# uv-light-sensor.net
KiCad netlist of a schematic drawn in EAGLE
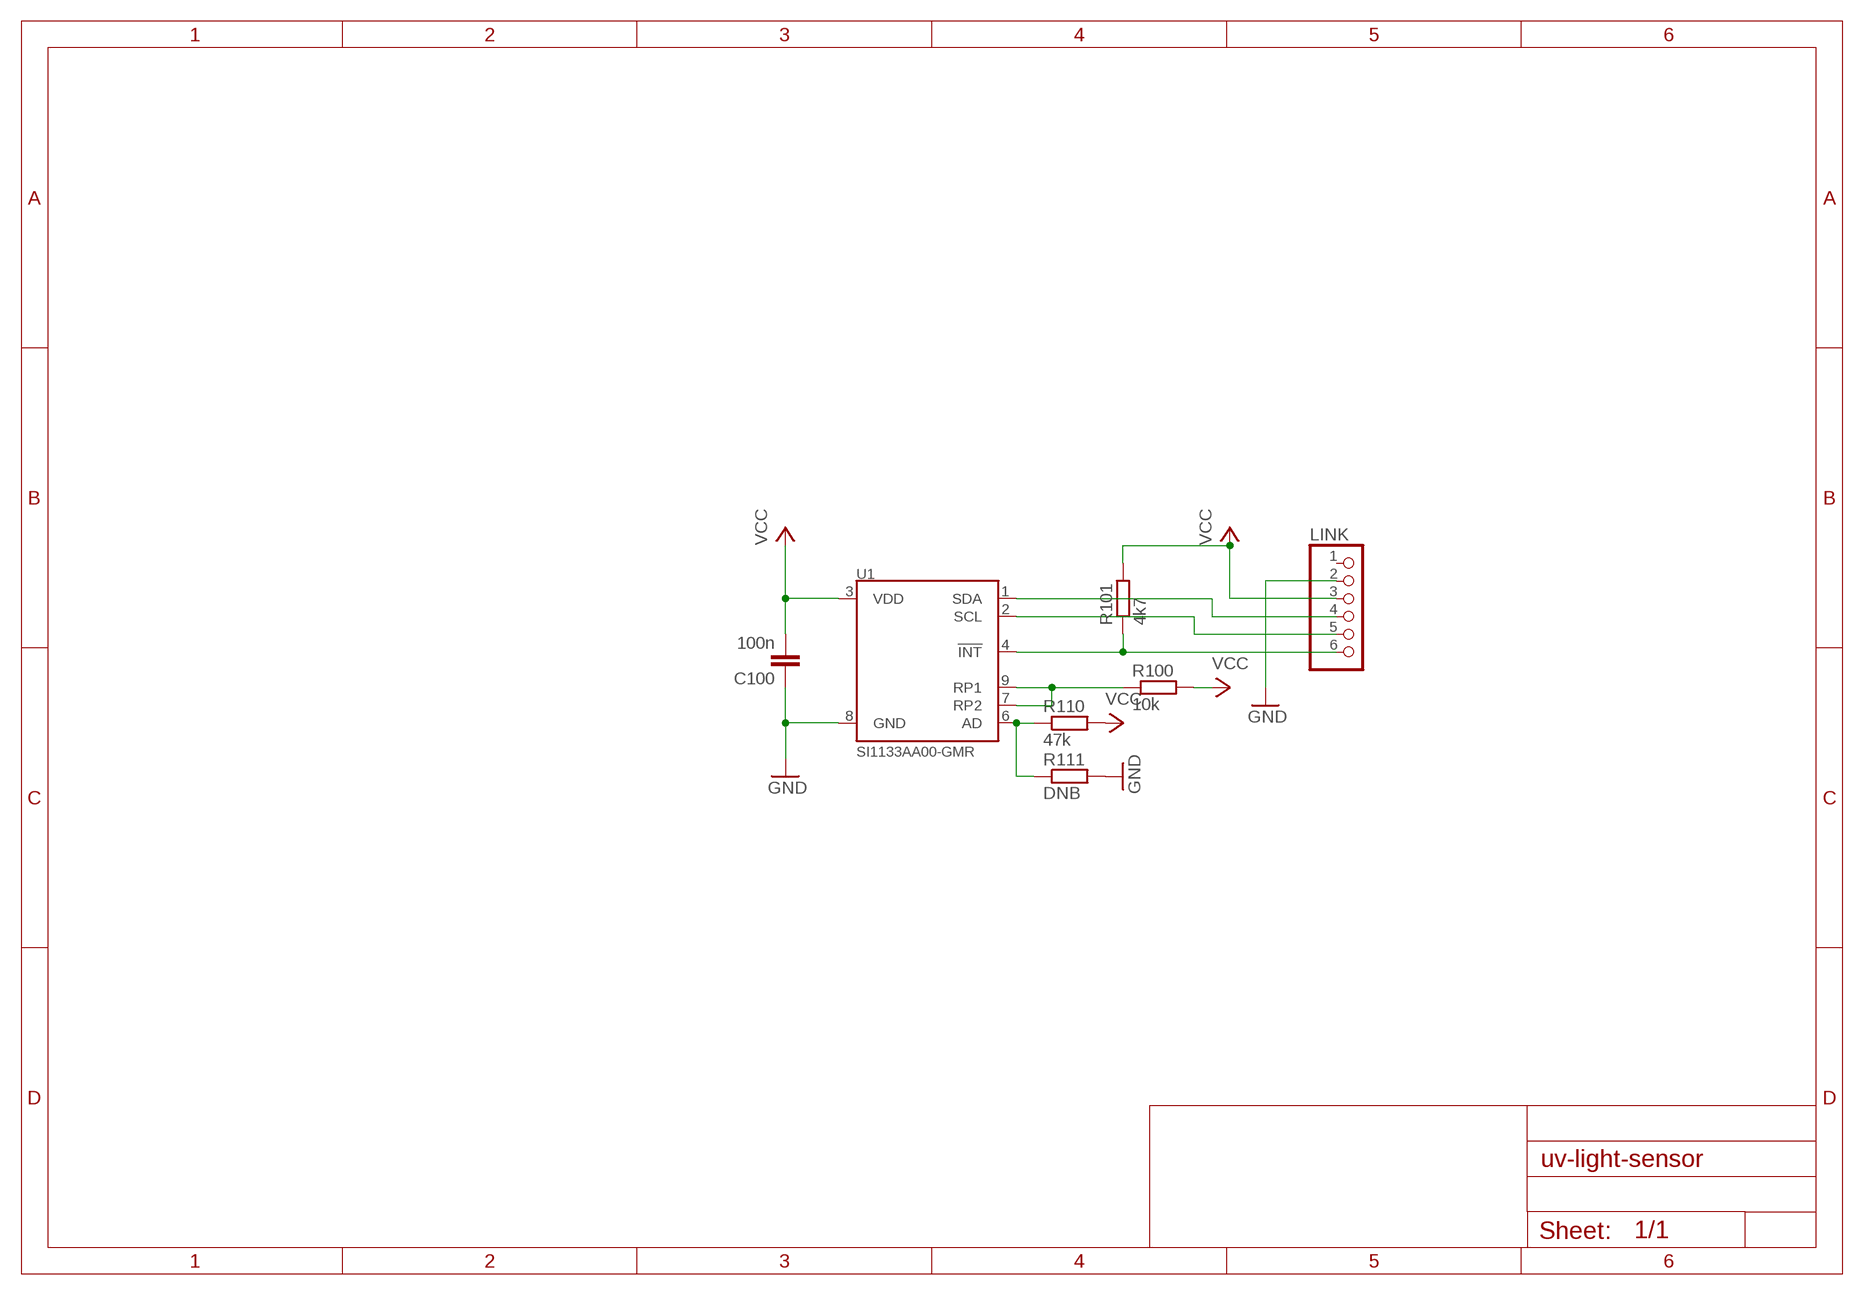
[diagram p0: schematic, sheet 1]

(export (version "E")
  (design (tool "Eeschema 10.0.6"))
  (components
    (comp (ref "C100")
      (value "100n")
      (footprint "eagle-import:C0603")
      (libsource (lib "eagle-import") (part "C-EUC0603"))
    )
    (comp (ref "LINK")
      (value "PINHD-1X6")
      (footprint "eagle-import:1X06")
      (libsource (lib "eagle-import") (part "PINHD-1X6"))
    )
    (comp (ref "R100")
      (value "10k")
      (footprint "eagle-import:R0603")
      (libsource (lib "eagle-import") (part "R-EU_R0603"))
    )
    (comp (ref "R101")
      (value "4k7")
      (footprint "eagle-import:R0603")
      (libsource (lib "eagle-import") (part "R-EU_R0603"))
    )
    (comp (ref "R110")
      (value "47k")
      (footprint "eagle-import:R0603")
      (libsource (lib "eagle-import") (part "R-EU_R0603"))
    )
    (comp (ref "R111")
      (value "DNB")
      (footprint "eagle-import:R0603")
      (libsource (lib "eagle-import") (part "R-EU_R0603"))
    )
    (comp (ref "U1")
      (value "SI1133AA00-GMR")
      (footprint "eagle-import:QFN-10_2MM")
      (libsource (lib "eagle-import") (part "SI1133AA00-GMR"))
    )
  )
  (nets
    (net (code "1") (name "GND") (class "Default")
      (node (ref "C100") (pin "1") (pinfunction "1_1") (pintype "passive"))
      (node (ref "LINK") (pin "2") (pinfunction "2_2") (pintype "passive"))
      (node (ref "R111") (pin "2") (pinfunction "2_2") (pintype "passive"))
      (node (ref "U1") (pin "8") (pinfunction "GND_8") (pintype "bidirectional"))
    )
    (net (code "2") (name "Net-(U1-AD)") (class "Default")
      (node (ref "R110") (pin "1") (pinfunction "1_1") (pintype "passive"))
      (node (ref "R111") (pin "1") (pinfunction "1_1") (pintype "passive"))
      (node (ref "U1") (pin "6") (pinfunction "AD_6") (pintype "bidirectional"))
    )
    (net (code "3") (name "Net-(U1-RP1)") (class "Default")
      (node (ref "R100") (pin "1") (pinfunction "1_1") (pintype "passive"))
      (node (ref "U1") (pin "7") (pinfunction "RP2_7") (pintype "bidirectional"))
      (node (ref "U1") (pin "9") (pinfunction "RP1_9") (pintype "bidirectional"))
    )
    (net (code "4") (name "Net-(U1-SCL)") (class "Default")
      (node (ref "LINK") (pin "5") (pinfunction "5_5") (pintype "passive"))
      (node (ref "U1") (pin "2") (pinfunction "SCL_2") (pintype "bidirectional"))
    )
    (net (code "5") (name "Net-(U1-SDA)") (class "Default")
      (node (ref "LINK") (pin "4") (pinfunction "4_4") (pintype "passive"))
      (node (ref "U1") (pin "1") (pinfunction "SDA_1") (pintype "bidirectional"))
    )
    (net (code "6") (name "Net-(U1-~{INT})") (class "Default")
      (node (ref "LINK") (pin "6") (pinfunction "6_6") (pintype "passive"))
      (node (ref "R101") (pin "1") (pinfunction "1_1") (pintype "passive"))
      (node (ref "U1") (pin "4") (pinfunction "~{INT}_4") (pintype "bidirectional"))
    )
    (net (code "7") (name "VCC") (class "Default")
      (node (ref "C100") (pin "2") (pinfunction "2_2") (pintype "passive"))
      (node (ref "LINK") (pin "3") (pinfunction "3_3") (pintype "passive"))
      (node (ref "R100") (pin "2") (pinfunction "2_2") (pintype "passive"))
      (node (ref "R101") (pin "2") (pinfunction "2_2") (pintype "passive"))
      (node (ref "R110") (pin "2") (pinfunction "2_2") (pintype "passive"))
      (node (ref "U1") (pin "3") (pinfunction "VDD_3") (pintype "bidirectional"))
    )
    (net (code "8") (name "unconnected-(LINK-Pad1)") (class "Default")
      (node (ref "LINK") (pin "1") (pinfunction "1_1") (pintype "passive"))
    )
  )
)
